# TankBoardSheet3.net
KiCad netlist of a schematic drawn in Altium Designer
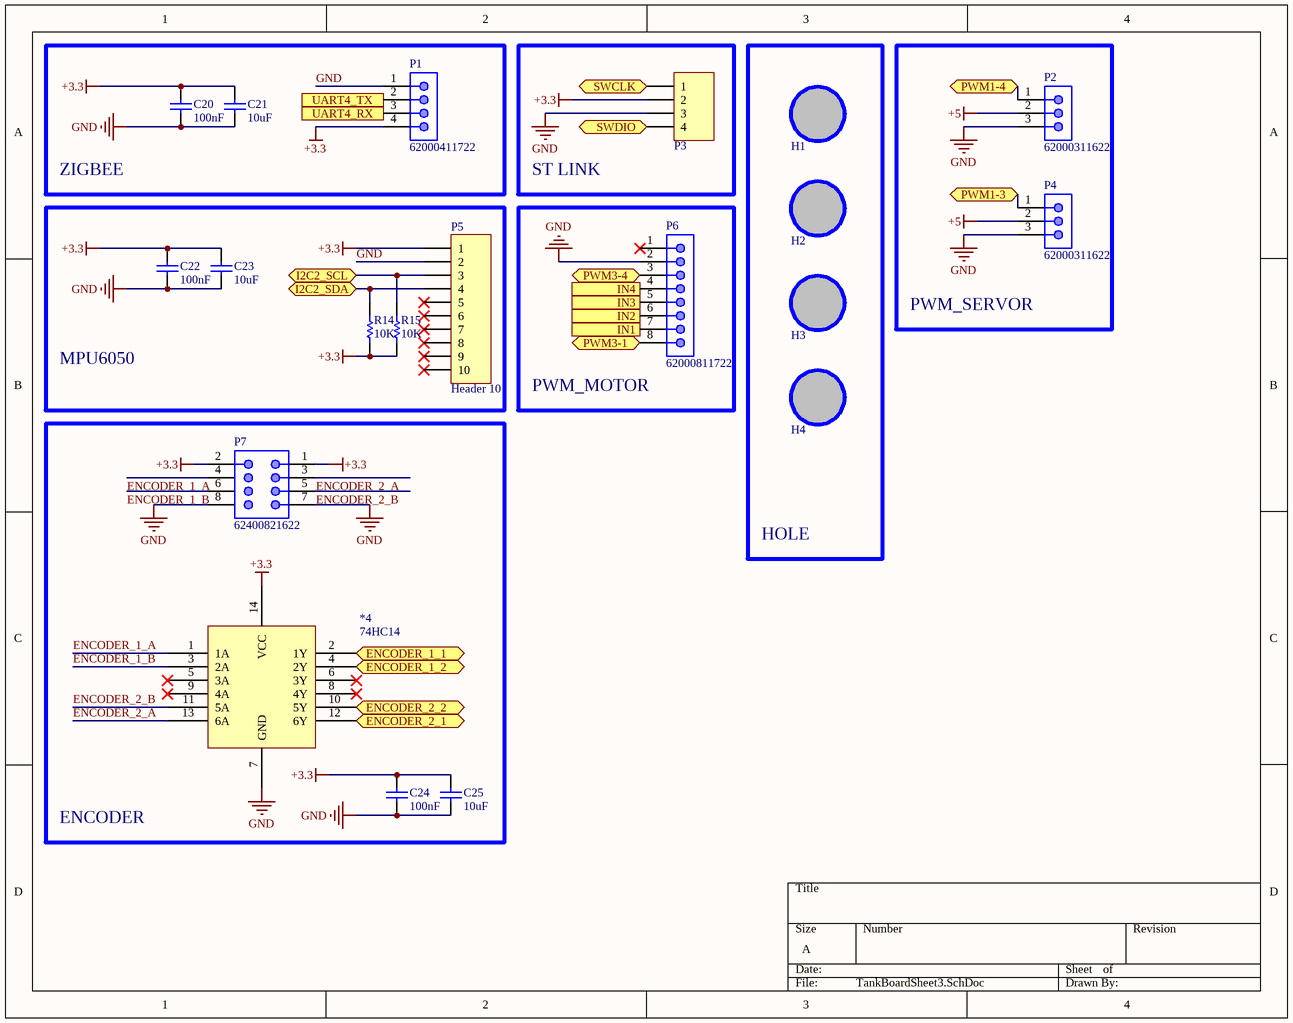
[diagram p0: TankBoardSheet3.SchDoc]

(export (version "E")
  (design (tool "Eeschema 10.0.6"))
  (components
    (comp (ref "*4")
      (value "74HC14")
      (footprint "SOIC108P600X170-14N")
      (libsource (lib "MiclsLib") (part "74HC14"))
    )
    (comp (ref "C20")
      (value "100nF")
      (footprint "CAP-SM-0603")
      (description "Capacitor")
      (fields (field (name "Comment") "Cap Non-Pol SMD"))
      (libsource (lib "PIF_Library") (part "Cap Non-Pol SMD"))
    )
    (comp (ref "C21")
      (value "10uF")
      (footprint "CAP-SM-0603")
      (description "Capacitor")
      (fields (field (name "Comment") "Cap Non-Pol SMD"))
      (libsource (lib "PIF_Library") (part "Cap Non-Pol SMD"))
    )
    (comp (ref "C22")
      (value "100nF")
      (footprint "CAP-SM-0603")
      (description "Capacitor")
      (fields (field (name "Comment") "Cap Non-Pol SMD"))
      (libsource (lib "PIF_Library") (part "Cap Non-Pol SMD"))
    )
    (comp (ref "C23")
      (value "10uF")
      (footprint "CAP-SM-0603")
      (description "Capacitor")
      (fields (field (name "Comment") "Cap Non-Pol SMD"))
      (libsource (lib "PIF_Library") (part "Cap Non-Pol SMD"))
    )
    (comp (ref "C24")
      (value "100nF")
      (footprint "CAP-SM-0603")
      (description "Capacitor")
      (fields (field (name "Comment") "Cap Non-Pol SMD"))
      (libsource (lib "PIF_Library") (part "Cap Non-Pol SMD"))
    )
    (comp (ref "C25")
      (value "10uF")
      (footprint "CAP-SM-0603")
      (description "Capacitor")
      (fields (field (name "Comment") "Cap Non-Pol SMD"))
      (libsource (lib "PIF_Library") (part "Cap Non-Pol SMD"))
    )
    (comp (ref "H1")
      (value "Hole")
      (footprint "LO KHOAN 3MM")
      (description "Hole 3mm")
      (libsource (lib "PIF_Library") (part "Hole"))
    )
    (comp (ref "H2")
      (value "Hole")
      (footprint "LO KHOAN 3MM")
      (description "Hole 3mm")
      (libsource (lib "PIF_Library") (part "Hole"))
    )
    (comp (ref "H3")
      (value "Hole")
      (footprint "LO KHOAN 3MM")
      (description "Hole 3mm")
      (libsource (lib "PIF_Library") (part "Hole"))
    )
    (comp (ref "H4")
      (value "Hole")
      (footprint "LO KHOAN 3MM")
      (description "Hole 3mm")
      (libsource (lib "PIF_Library") (part "Hole"))
    )
    (comp (ref "P1")
      (value "62000411722")
      (footprint "62000411722")
      (description "WR-WTB THT Male Horizontal Shrouded Header, pitch 2mm, 4p")
      (fields (field (name "PUBLISHER") "Wurth Elektronik"))
      (libsource (lib "653008114822_Altium_WR-WTB_rev20a") (part "62000411722"))
    )
    (comp (ref "P2")
      (value "62000311622")
      (footprint "62000311622")
      (description "WR-WTB Male Vertical Shrouded Header, pitch 2mm, 3p")
      (fields (field (name "PUBLISHER") "Wurth Elektronik"))
      (libsource (lib "653008114822_Altium_WR-WTB_rev20a") (part "62000311622"))
    )
    (comp (ref "P3")
      (value "Header 4")
      (footprint "JP4")
      (description "Header, 4-Pin")
      (fields (field (name "PUBLISHER") "Altium Limited"))
      (libsource (lib "PIF_Library") (part "Header 4"))
    )
    (comp (ref "P4")
      (value "62000311622")
      (footprint "62000311622")
      (description "WR-WTB Male Vertical Shrouded Header, pitch 2mm, 3p")
      (fields (field (name "PUBLISHER") "Wurth Elektronik"))
      (libsource (lib "653008114822_Altium_WR-WTB_rev20a") (part "62000311622"))
    )
    (comp (ref "P5")
      (value "Header 10")
      (footprint "HDR1X10")
      (description "Header, 10-Pin")
      (fields (field (name "PUBLISHER") "Altium Limited"))
      (libsource (lib "Miscellaneous Connectors") (part "Header 10"))
    )
    (comp (ref "P6")
      (value "62000811722")
      (footprint "62000811722")
      (description "WR-WTB THT Male Horizontal Shrouded Header, pitch 2mm, 8p")
      (fields (field (name "PUBLISHER") "Wurth Elektronik"))
      (libsource (lib "653008114822_Altium_WR-WTB_rev20a") (part "62000811722"))
    )
    (comp (ref "P7")
      (value "62400821622")
      (footprint "62400821622")
      (description "WR-WTB THT Male Vertical Shrouded Header with positive locking, Dual Row, pitch 2mm, 8p")
      (fields (field (name "PUBLISHER") "Wurth Elektronik"))
      (libsource (lib "653008114822_Altium_WR-WTB_rev20a") (part "62400821622"))
    )
    (comp (ref "R14")
      (value "10K")
      (footprint "RES-SM-0603")
      (description "Resistor")
      (fields (field (name "Comment") "RESISTOR SMD"))
      (libsource (lib "PIF_Library") (part "RESISTOR SMD"))
    )
    (comp (ref "R15")
      (value "10K")
      (footprint "RES-SM-0603")
      (description "Resistor")
      (fields (field (name "Comment") "RESISTOR SMD"))
      (libsource (lib "PIF_Library") (part "RESISTOR SMD"))
    )
  )
  (nets
    (net (code "1") (name "+3.3") (class "Default")
      (node (ref "*4") (pin "14") (pinfunction "VCC_14") (pintype "passive"))
      (node (ref "C20") (pin "1") (pinfunction "1_1") (pintype "passive"))
      (node (ref "C21") (pin "1") (pinfunction "1_1") (pintype "passive"))
      (node (ref "C22") (pin "1") (pinfunction "1_1") (pintype "passive"))
      (node (ref "C23") (pin "1") (pinfunction "1_1") (pintype "passive"))
      (node (ref "C24") (pin "1") (pinfunction "1_1") (pintype "passive"))
      (node (ref "C25") (pin "1") (pinfunction "1_1") (pintype "passive"))
      (node (ref "P1") (pin "4") (pinfunction "4_4") (pintype "passive"))
      (node (ref "P3") (pin "2") (pinfunction "2_2") (pintype "passive"))
      (node (ref "P5") (pin "1") (pinfunction "1_1") (pintype "passive"))
      (node (ref "P7") (pin "1") (pinfunction "1_1") (pintype "passive"))
      (node (ref "P7") (pin "2") (pinfunction "2_2") (pintype "passive"))
      (node (ref "R14") (pin "1") (pinfunction "1_1") (pintype "passive"))
      (node (ref "R15") (pin "1") (pinfunction "1_1") (pintype "passive"))
    )
    (net (code "2") (name "+5") (class "Default")
      (node (ref "P2") (pin "2") (pinfunction "2_2") (pintype "passive"))
      (node (ref "P4") (pin "2") (pinfunction "2_2") (pintype "passive"))
    )
    (net (code "3") (name "/ENCODER_1_1") (class "Default")
      (node (ref "*4") (pin "2") (pinfunction "1Y_2") (pintype "passive"))
    )
    (net (code "4") (name "/ENCODER_1_2") (class "Default")
      (node (ref "*4") (pin "4") (pinfunction "2Y_4") (pintype "passive"))
    )
    (net (code "5") (name "/ENCODER_1_A") (class "Default")
      (node (ref "*4") (pin "1") (pinfunction "1A_1") (pintype "passive"))
      (node (ref "P7") (pin "4") (pinfunction "4_4") (pintype "passive"))
    )
    (net (code "6") (name "/ENCODER_1_B") (class "Default")
      (node (ref "*4") (pin "3") (pinfunction "2A_3") (pintype "passive"))
      (node (ref "P7") (pin "6") (pinfunction "6_6") (pintype "passive"))
    )
    (net (code "7") (name "/ENCODER_2_1") (class "Default")
      (node (ref "*4") (pin "12") (pinfunction "6Y_12") (pintype "passive"))
    )
    (net (code "8") (name "/ENCODER_2_2") (class "Default")
      (node (ref "*4") (pin "10") (pinfunction "5Y_10") (pintype "passive"))
    )
    (net (code "9") (name "/ENCODER_2_A") (class "Default")
      (node (ref "*4") (pin "13") (pinfunction "6A_13") (pintype "passive"))
      (node (ref "P7") (pin "3") (pinfunction "3_3") (pintype "passive"))
    )
    (net (code "10") (name "/ENCODER_2_B") (class "Default")
      (node (ref "*4") (pin "11") (pinfunction "5A_11") (pintype "passive"))
      (node (ref "P7") (pin "5") (pinfunction "5_5") (pintype "passive"))
    )
    (net (code "11") (name "/I2C2_SCL") (class "Default")
      (node (ref "P5") (pin "3") (pinfunction "3_3") (pintype "passive"))
      (node (ref "R15") (pin "2") (pinfunction "2_2") (pintype "passive"))
    )
    (net (code "12") (name "/I2C2_SDA") (class "Default")
      (node (ref "P5") (pin "4") (pinfunction "4_4") (pintype "passive"))
      (node (ref "R14") (pin "2") (pinfunction "2_2") (pintype "passive"))
    )
    (net (code "13") (name "/IN1") (class "Default")
      (node (ref "P6") (pin "7") (pinfunction "7_7") (pintype "passive"))
    )
    (net (code "14") (name "/IN2") (class "Default")
      (node (ref "P6") (pin "6") (pinfunction "6_6") (pintype "passive"))
    )
    (net (code "15") (name "/IN3") (class "Default")
      (node (ref "P6") (pin "5") (pinfunction "5_5") (pintype "passive"))
    )
    (net (code "16") (name "/IN4") (class "Default")
      (node (ref "P6") (pin "4") (pinfunction "4_4") (pintype "passive"))
    )
    (net (code "17") (name "/PWM1-3") (class "Default")
      (node (ref "P4") (pin "1") (pinfunction "1_1") (pintype "passive"))
    )
    (net (code "18") (name "/PWM1-4") (class "Default")
      (node (ref "P2") (pin "1") (pinfunction "1_1") (pintype "passive"))
    )
    (net (code "19") (name "/PWM3-1") (class "Default")
      (node (ref "P6") (pin "8") (pinfunction "8_8") (pintype "passive"))
    )
    (net (code "20") (name "/PWM3-4") (class "Default")
      (node (ref "P6") (pin "3") (pinfunction "3_3") (pintype "passive"))
    )
    (net (code "21") (name "/SWCLK") (class "Default")
      (node (ref "P3") (pin "1") (pinfunction "1_1") (pintype "passive"))
    )
    (net (code "22") (name "/SWDIO") (class "Default")
      (node (ref "P3") (pin "4") (pinfunction "4_4") (pintype "passive"))
    )
    (net (code "23") (name "/UART4_RX") (class "Default")
      (node (ref "P1") (pin "3") (pinfunction "3_3") (pintype "passive"))
    )
    (net (code "24") (name "/UART4_TX") (class "Default")
      (node (ref "P1") (pin "2") (pinfunction "2_2") (pintype "passive"))
    )
    (net (code "25") (name "GND") (class "Default")
      (node (ref "*4") (pin "7") (pinfunction "GND_7") (pintype "passive"))
      (node (ref "C20") (pin "2") (pinfunction "2_2") (pintype "passive"))
      (node (ref "C21") (pin "2") (pinfunction "2_2") (pintype "passive"))
      (node (ref "C22") (pin "2") (pinfunction "2_2") (pintype "passive"))
      (node (ref "C23") (pin "2") (pinfunction "2_2") (pintype "passive"))
      (node (ref "C24") (pin "2") (pinfunction "2_2") (pintype "passive"))
      (node (ref "C25") (pin "2") (pinfunction "2_2") (pintype "passive"))
      (node (ref "P1") (pin "1") (pinfunction "1_1") (pintype "passive"))
      (node (ref "P2") (pin "3") (pinfunction "3_3") (pintype "passive"))
      (node (ref "P3") (pin "3") (pinfunction "3_3") (pintype "passive"))
      (node (ref "P4") (pin "3") (pinfunction "3_3") (pintype "passive"))
      (node (ref "P5") (pin "2") (pinfunction "2_2") (pintype "passive"))
      (node (ref "P6") (pin "2") (pinfunction "2_2") (pintype "passive"))
      (node (ref "P7") (pin "7") (pinfunction "7_7") (pintype "passive"))
      (node (ref "P7") (pin "8") (pinfunction "8_8") (pintype "passive"))
    )
    (net (code "26") (name "unconnected-(*4-3A-Pad5)") (class "Default")
      (node (ref "*4") (pin "5") (pinfunction "3A_5") (pintype "passive+no_connect"))
    )
    (net (code "27") (name "unconnected-(*4-3Y-Pad6)") (class "Default")
      (node (ref "*4") (pin "6") (pinfunction "3Y_6") (pintype "passive+no_connect"))
    )
    (net (code "28") (name "unconnected-(*4-4A-Pad9)") (class "Default")
      (node (ref "*4") (pin "9") (pinfunction "4A_9") (pintype "passive+no_connect"))
    )
    (net (code "29") (name "unconnected-(*4-4Y-Pad8)") (class "Default")
      (node (ref "*4") (pin "8") (pinfunction "4Y_8") (pintype "passive+no_connect"))
    )
    (net (code "30") (name "unconnected-(H1-Pad1)") (class "Default")
      (node (ref "H1") (pin "1") (pinfunction "1_1") (pintype "passive"))
    )
    (net (code "31") (name "unconnected-(H2-Pad1)") (class "Default")
      (node (ref "H2") (pin "1") (pinfunction "1_1") (pintype "passive"))
    )
    (net (code "32") (name "unconnected-(H3-Pad1)") (class "Default")
      (node (ref "H3") (pin "1") (pinfunction "1_1") (pintype "passive"))
    )
    (net (code "33") (name "unconnected-(H4-Pad1)") (class "Default")
      (node (ref "H4") (pin "1") (pinfunction "1_1") (pintype "passive"))
    )
    (net (code "34") (name "unconnected-(P5-Pad5)") (class "Default")
      (node (ref "P5") (pin "5") (pinfunction "5_5") (pintype "passive+no_connect"))
    )
    (net (code "35") (name "unconnected-(P5-Pad6)") (class "Default")
      (node (ref "P5") (pin "6") (pinfunction "6_6") (pintype "passive+no_connect"))
    )
    (net (code "36") (name "unconnected-(P5-Pad7)") (class "Default")
      (node (ref "P5") (pin "7") (pinfunction "7_7") (pintype "passive+no_connect"))
    )
    (net (code "37") (name "unconnected-(P5-Pad8)") (class "Default")
      (node (ref "P5") (pin "8") (pinfunction "8_8") (pintype "passive+no_connect"))
    )
    (net (code "38") (name "unconnected-(P5-Pad9)") (class "Default")
      (node (ref "P5") (pin "9") (pinfunction "9_9") (pintype "passive+no_connect"))
    )
    (net (code "39") (name "unconnected-(P5-Pad10)") (class "Default")
      (node (ref "P5") (pin "10") (pinfunction "10_10") (pintype "passive+no_connect"))
    )
    (net (code "40") (name "unconnected-(P6-Pad1)") (class "Default")
      (node (ref "P6") (pin "1") (pinfunction "1_1") (pintype "passive+no_connect"))
    )
  )
)
